# schematic.net
KiCad netlist of a schematic drawn in EAGLE
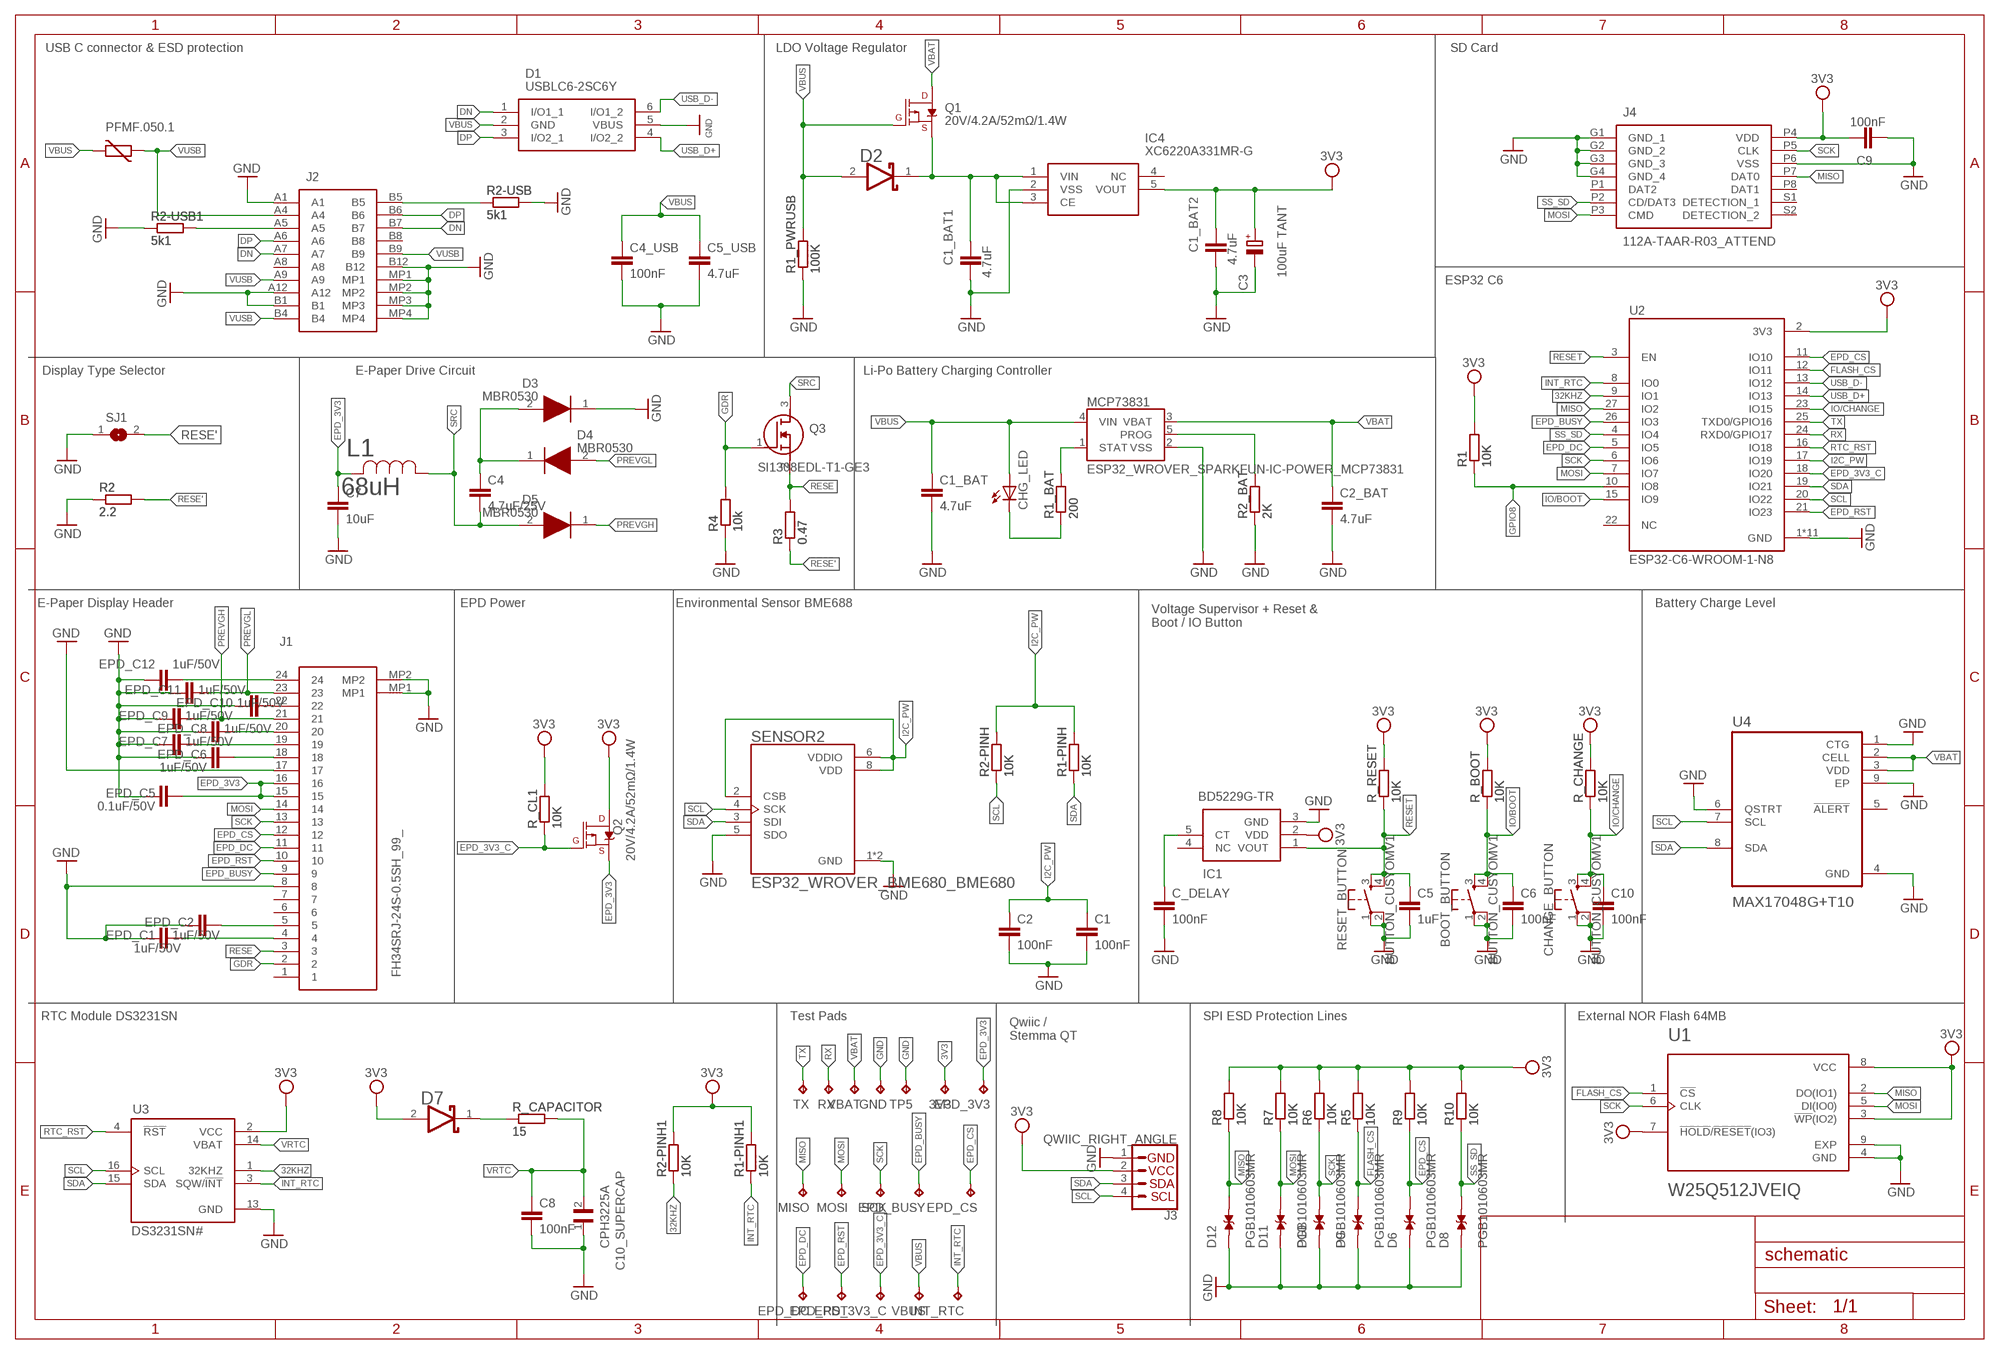
[diagram p0: schematic, sheet 1]

(export (version "E")
  (design (tool "Eeschema 10.0.6"))
  (components
    (comp (ref "3V3")
      (value "TPTP20R")
      (footprint "eagle-import:TP20R")
      (libsource (lib "eagle-import") (part "TPTP20R"))
    )
    (comp (ref "BOOT_BUTTON")
      (value "BUTTON_CUSYOMV1")
      (footprint "eagle-import:MYBUTTON")
      (libsource (lib "eagle-import") (part "BUTTON_CUSYOMV1"))
    )
    (comp (ref "C1")
      (value "100nF")
      (footprint "eagle-import:EAGLE-LTSPICE_C0402")
      (libsource (lib "eagle-import") (part "ESP32_WROVER_EAGLE-LTSPICE_CC0402"))
    )
    (comp (ref "C1_BAT")
      (value "4.7uF")
      (footprint "eagle-import:EAGLE-LTSPICE_C0402")
      (libsource (lib "eagle-import") (part "ESP32_WROVER_EAGLE-LTSPICE_CC0402"))
    )
    (comp (ref "C1_BAT1")
      (value "4.7uF")
      (footprint "eagle-import:ESP32_WROVER_EAGLE-LTSPICE_C0402")
      (libsource (lib "eagle-import") (part "DeskAssistant v19 v1_vf.dFvje_iDQXiLOtX_eNBvag_EAGLE-LTSPICE_CC0402"))
    )
    (comp (ref "C1_BAT2")
      (value "4.7uF")
      (footprint "eagle-import:ESP32_WROVER_EAGLE-LTSPICE_C0402")
      (libsource (lib "eagle-import") (part "DeskAssistant v19 v1_vf.dFvje_iDQXiLOtX_eNBvag_EAGLE-LTSPICE_CC0402"))
    )
    (comp (ref "C2")
      (value "100nF")
      (footprint "eagle-import:EAGLE-LTSPICE_C0402")
      (libsource (lib "eagle-import") (part "ESP32_WROVER_EAGLE-LTSPICE_CC0402"))
    )
    (comp (ref "C2_BAT")
      (value "4.7uF")
      (footprint "eagle-import:EAGLE-LTSPICE_C0402")
      (libsource (lib "eagle-import") (part "ESP32_WROVER_EAGLE-LTSPICE_CC0402"))
    )
    (comp (ref "C3")
      (value "100uF TANT")
      (footprint "eagle-import:RCL_CT3528")
      (libsource (lib "eagle-import") (part "RCL_CPOL-EUCT3528"))
    )
    (comp (ref "C4")
      (value "4.7uF/25V")
      (footprint "eagle-import:EAGLE-LTSPICE_C0402")
      (libsource (lib "eagle-import") (part "ESP32_WROVER_EAGLE-LTSPICE_CC0402"))
    )
    (comp (ref "C4_USB")
      (value "100nF")
      (footprint "eagle-import:EAGLE-LTSPICE_C0402")
      (libsource (lib "eagle-import") (part "EAGLE-LTSPICE_CC0402"))
    )
    (comp (ref "C5")
      (value "1uF")
      (footprint "eagle-import:EAGLE-LTSPICE_C0402")
      (libsource (lib "eagle-import") (part "ESP32_WROVER_EAGLE-LTSPICE_CC0402"))
    )
    (comp (ref "C5_USB")
      (value "4.7uF")
      (footprint "eagle-import:EAGLE-LTSPICE_C0402")
      (libsource (lib "eagle-import") (part "EAGLE-LTSPICE_CC0402"))
    )
    (comp (ref "C6")
      (value "100nF")
      (footprint "eagle-import:EAGLE-LTSPICE_C0402")
      (libsource (lib "eagle-import") (part "ESP32_WROVER_EAGLE-LTSPICE_CC0402"))
    )
    (comp (ref "C7")
      (value "10uF")
      (footprint "eagle-import:EAGLE-LTSPICE_C0402")
      (libsource (lib "eagle-import") (part "ESP32_WROVER_EAGLE-LTSPICE_CC0402"))
    )
    (comp (ref "C8")
      (value "100nF")
      (footprint "eagle-import:EAGLE-LTSPICE_C0402")
      (libsource (lib "eagle-import") (part "ESP32_WROVER_EAGLE-LTSPICE_CC0402"))
    )
    (comp (ref "C9")
      (value "100nF")
      (footprint "eagle-import:ESP32_WROVER_EAGLE-LTSPICE_C0402")
      (libsource (lib "eagle-import") (part "DeskAssistant v19 v1_vf.dFvje_iDQXiLOtX_eNBvag_EAGLE-LTSPICE_CC0402"))
    )
    (comp (ref "C10")
      (value "100nF")
      (footprint "eagle-import:EAGLE-LTSPICE_C0402")
      (libsource (lib "eagle-import") (part "ESP32_WROVER_EAGLE-LTSPICE_CC0402"))
    )
    (comp (ref "C10_SUPERCAP")
      (value "CPH3225A")
      (footprint "eagle-import:CAPCP3225X100N")
      (fields (field (name "MF") "Seiko Instruments"))
      (libsource (lib "eagle-import") (part "CPH3225A"))
    )
    (comp (ref "CHANGE_BUTTON")
      (value "BUTTON_CUSYOMV1")
      (footprint "eagle-import:MYBUTTON")
      (libsource (lib "eagle-import") (part "BUTTON_CUSYOMV1"))
    )
    (comp (ref "CHG_LED")
      (value "ADAFRUIT_LEDCHIP-LED0603")
      (footprint "eagle-import:ADAFRUIT_CHIP-LED0603")
      (libsource (lib "eagle-import") (part "ADAFRUIT_LEDCHIP-LED0603"))
    )
    (comp (ref "C_DELAY")
      (value "100nF")
      (footprint "eagle-import:EAGLE-LTSPICE_C0402")
      (libsource (lib "eagle-import") (part "ESP32_WROVER_EAGLE-LTSPICE_CC0402"))
    )
    (comp (ref "D1")
      (value "USBLC6-2SC6Y")
      (footprint "eagle-import:SOT95P280X145-6N")
      (fields (field (name "MF") "STMicroelectronics"))
      (libsource (lib "eagle-import") (part "USBLC6-2SC6Y"))
    )
    (comp (ref "D2")
      (value "ESP32_WROVER_AVX---SD0805S020S1R0_AVX_SD0805S020S1R0_0_0AVX_SD0805S020S1R0_0_0")
      (footprint "eagle-import:ESP32_WROVER_AVX---SD0805S020S1R0_AVX_SD0805S020S1R0_0")
      (fields
        (field (name "DIGIKEY_PART_NUMBER") "478-7800-1-ND")
        (field (name "MF") "AVX")
        (field (name "MOUSER_PART_NUMBER") "581-SD0805S020S1R0")
      )
      (libsource (lib "eagle-import") (part "ESP32_WROVER_AVX---SD0805S020S1R0_AVX_SD0805S020S1R0_0_0AVX_SD0805S020S1R0_0_0"))
    )
    (comp (ref "D3")
      (value "MBR0530")
      (footprint "eagle-import:SOD3716X135N")
      (fields (field (name "MF") "ON Semiconductor"))
      (libsource (lib "eagle-import") (part "MBR0530"))
    )
    (comp (ref "D4")
      (value "MBR0530")
      (footprint "eagle-import:SOD3716X135N")
      (fields (field (name "MF") "ON Semiconductor"))
      (libsource (lib "eagle-import") (part "MBR0530"))
    )
    (comp (ref "D5")
      (value "MBR0530")
      (footprint "eagle-import:SOD3716X135N")
      (fields (field (name "MF") "ON Semiconductor"))
      (libsource (lib "eagle-import") (part "MBR0530"))
    )
    (comp (ref "D6")
      (value "PGB1010603MR")
      (footprint "eagle-import:DIOC1608X36N")
      (fields (field (name "MF") "Littelfuse Inc."))
      (libsource (lib "eagle-import") (part "PGB1010603MR"))
    )
    (comp (ref "D7")
      (value "ESP32_WROVER_AVX---SD0805S020S1R0_AVX_SD0805S020S1R0_0_0AVX_SD0805S020S1R0_0_0")
      (footprint "eagle-import:ESP32_WROVER_AVX---SD0805S020S1R0_AVX_SD0805S020S1R0_0")
      (fields
        (field (name "DIGIKEY_PART_NUMBER") "478-7800-1-ND")
        (field (name "MF") "AVX")
        (field (name "MOUSER_PART_NUMBER") "581-SD0805S020S1R0")
      )
      (libsource (lib "eagle-import") (part "ESP32_WROVER_AVX---SD0805S020S1R0_AVX_SD0805S020S1R0_0_0AVX_SD0805S020S1R0_0_0"))
    )
    (comp (ref "D8")
      (value "PGB1010603MR")
      (footprint "eagle-import:DIOC1608X36N")
      (fields (field (name "MF") "Littelfuse Inc."))
      (libsource (lib "eagle-import") (part "PGB1010603MR"))
    )
    (comp (ref "D9")
      (value "PGB1010603MR")
      (footprint "eagle-import:DIOC1608X36N")
      (fields (field (name "MF") "Littelfuse Inc."))
      (libsource (lib "eagle-import") (part "PGB1010603MR"))
    )
    (comp (ref "D10")
      (value "PGB1010603MR")
      (footprint "eagle-import:DIOC1608X36N")
      (fields (field (name "MF") "Littelfuse Inc."))
      (libsource (lib "eagle-import") (part "PGB1010603MR"))
    )
    (comp (ref "D11")
      (value "PGB1010603MR")
      (footprint "eagle-import:DIOC1608X36N")
      (fields (field (name "MF") "Littelfuse Inc."))
      (libsource (lib "eagle-import") (part "PGB1010603MR"))
    )
    (comp (ref "D12")
      (value "PGB1010603MR")
      (footprint "eagle-import:DIOC1608X36N")
      (fields (field (name "MF") "Littelfuse Inc."))
      (libsource (lib "eagle-import") (part "PGB1010603MR"))
    )
    (comp (ref "EPD_3V3")
      (value "TPTP20R")
      (footprint "eagle-import:TP20R")
      (libsource (lib "eagle-import") (part "TPTP20R"))
    )
    (comp (ref "EPD_3V3_C")
      (value "TPTP20R")
      (footprint "eagle-import:TP20R")
      (libsource (lib "eagle-import") (part "TPTP20R"))
    )
    (comp (ref "EPD_BUSY")
      (value "TPTP20R")
      (footprint "eagle-import:TP20R")
      (libsource (lib "eagle-import") (part "TPTP20R"))
    )
    (comp (ref "EPD_C1")
      (value "1uF/50V")
      (footprint "eagle-import:EAGLE-LTSPICE_C0402")
      (libsource (lib "eagle-import") (part "ESP32_WROVER_EAGLE-LTSPICE_CC0402"))
    )
    (comp (ref "EPD_C2")
      (value "1uF/50V")
      (footprint "eagle-import:EAGLE-LTSPICE_C0402")
      (libsource (lib "eagle-import") (part "ESP32_WROVER_EAGLE-LTSPICE_CC0402"))
    )
    (comp (ref "EPD_C5")
      (value "0.1uF/50V")
      (footprint "eagle-import:EAGLE-LTSPICE_C0402")
      (libsource (lib "eagle-import") (part "ESP32_WROVER_EAGLE-LTSPICE_CC0402"))
    )
    (comp (ref "EPD_C6")
      (value "1uF/50V")
      (footprint "eagle-import:EAGLE-LTSPICE_C0402")
      (libsource (lib "eagle-import") (part "ESP32_WROVER_EAGLE-LTSPICE_CC0402"))
    )
    (comp (ref "EPD_C7")
      (value "1uF/50V")
      (footprint "eagle-import:EAGLE-LTSPICE_C0402")
      (libsource (lib "eagle-import") (part "ESP32_WROVER_EAGLE-LTSPICE_CC0402"))
    )
    (comp (ref "EPD_C8")
      (value "1uF/50V")
      (footprint "eagle-import:EAGLE-LTSPICE_C0402")
      (libsource (lib "eagle-import") (part "ESP32_WROVER_EAGLE-LTSPICE_CC0402"))
    )
    (comp (ref "EPD_C9")
      (value "1uF/50V")
      (footprint "eagle-import:EAGLE-LTSPICE_C0402")
      (libsource (lib "eagle-import") (part "ESP32_WROVER_EAGLE-LTSPICE_CC0402"))
    )
    (comp (ref "EPD_C10")
      (value "1uF/50V")
      (footprint "eagle-import:EAGLE-LTSPICE_C0402")
      (libsource (lib "eagle-import") (part "ESP32_WROVER_EAGLE-LTSPICE_CC0402"))
    )
    (comp (ref "EPD_C11")
      (value "1uF/50V")
      (footprint "eagle-import:EAGLE-LTSPICE_C0402")
      (libsource (lib "eagle-import") (part "ESP32_WROVER_EAGLE-LTSPICE_CC0402"))
    )
    (comp (ref "EPD_C12")
      (value "1uF/50V")
      (footprint "eagle-import:EAGLE-LTSPICE_C0402")
      (libsource (lib "eagle-import") (part "ESP32_WROVER_EAGLE-LTSPICE_CC0402"))
    )
    (comp (ref "EPD_CS")
      (value "TPTP20R")
      (footprint "eagle-import:TP20R")
      (libsource (lib "eagle-import") (part "TPTP20R"))
    )
    (comp (ref "EPD_DC")
      (value "TPTP20R")
      (footprint "eagle-import:TP20R")
      (libsource (lib "eagle-import") (part "TPTP20R"))
    )
    (comp (ref "EPD_RST")
      (value "TPTP20R")
      (footprint "eagle-import:TP20R")
      (libsource (lib "eagle-import") (part "TPTP20R"))
    )
    (comp (ref "GND")
      (value "TPTP20R")
      (footprint "eagle-import:TP20R")
      (libsource (lib "eagle-import") (part "TPTP20R"))
    )
    (comp (ref "IC1")
      (value "BD5229G-TR")
      (footprint "eagle-import:SOT95P280X125-5N")
      (fields (field (name "MOUSER_PART_NUMBER") "755-BD5229G-TR"))
      (libsource (lib "eagle-import") (part "BD5229G-TR"))
    )
    (comp (ref "IC4")
      (value "XC6220A331MR-G")
      (footprint "eagle-import:SOT95P280X120-5N")
      (fields (field (name "MOUSER_PART_NUMBER") "865-XC6220A331MR-G"))
      (libsource (lib "eagle-import") (part "XC6220A331MR-G"))
    )
    (comp (ref "INT_RTC")
      (value "TPTP20R")
      (footprint "eagle-import:TP20R")
      (libsource (lib "eagle-import") (part "TPTP20R"))
    )
    (comp (ref "J1")
      (value "FH34SRJ-24S-0.5SH_99_")
      (footprint "eagle-import:FH34SRJ24S05SH99")
      (fields
        (field (name "MANUFACTURER_PART_NUMBER") "FH34SRJ-24S-0.5SH(99)")
        (field (name "MOUSER_PART_NUMBER") "798-FH34SRJ24S05SH99")
      )
      (libsource (lib "eagle-import") (part "FH34SRJ-24S-0.5SH_99_"))
    )
    (comp (ref "J2")
      (value "SAMACSYS_PARTS_USB4110-GF-A")
      (footprint "eagle-import:SAMACSYS_PARTS_USB4110GFA")
      (fields
        (field (name "MANUFACTURER_PART_NUMBER") "USB4110-GF-A")
        (field (name "MOUSER_PART_NUMBER") "640-USB4110-GF-A")
      )
      (libsource (lib "eagle-import") (part "SAMACSYS_PARTS_USB4110-GF-A"))
    )
    (comp (ref "J3")
      (value "QWIIC_RIGHT_ANGLE")
      (footprint "eagle-import:JST04_1MM_RA")
      (libsource (lib "eagle-import") (part "QWIIC_CONNECTORJS-1MM"))
    )
    (comp (ref "J4")
      (value "112A-TAAR-R03_ATTEND")
      (footprint "eagle-import:112ATAARR03ATTEND")
      (fields (field (name "MANUFACTURER_PART_NUMBER") "112A-TAAR-R03 ATTEND"))
      (libsource (lib "eagle-import") (part "112A-TAAR-R03_ATTEND"))
    )
    (comp (ref "L1")
      (value "68uH")
      (footprint "eagle-import:IND_4828-WE-TPC_WRE")
      (fields
        (field (name "MANUFACTURER_PART_NUMBER") "744043680")
        (field (name "COPYRIGHT") "Copyright (C) 2024 Ultra Librarian. All rights reserved.")
      )
      (libsource (lib "eagle-import") (part "744043680IND_4828-WE-TPC_WRE"))
    )
    (comp (ref "MCP73831")
      (value "ESP32_WROVER_SPARKFUN-IC-POWER_MCP73831")
      (footprint "eagle-import:ESP32_WROVER_SPARKFUN-IC-POWER_SOT23-5")
      (libsource (lib "eagle-import") (part "ESP32_WROVER_SPARKFUN-IC-POWER_MCP73831"))
    )
    (comp (ref "MISO")
      (value "TPTP20R")
      (footprint "eagle-import:TP20R")
      (libsource (lib "eagle-import") (part "TPTP20R"))
    )
    (comp (ref "MOSI")
      (value "TPTP20R")
      (footprint "eagle-import:TP20R")
      (libsource (lib "eagle-import") (part "TPTP20R"))
    )
    (comp (ref "PFMF.050.1")
      (value "ESP32C6_VARISTORCN1812")
      (footprint "eagle-import:ESP32C6_VARISTOR_CT_CN1812")
      (libsource (lib "eagle-import") (part "ESP32C6_VARISTORCN1812"))
    )
    (comp (ref "Q1")
      (value "20V/4.2A/52mΩ/1.4W")
      (footprint "eagle-import:ESP32_WROVER_SPARKFUN-DISCRETESEMI_SOT23-3")
      (libsource (lib "eagle-import") (part "ESP32_WROVER_SPARKFUN-DISCRETESEMI_MOSFET_PCH-DMG2305UX-7"))
    )
    (comp (ref "Q2")
      (value "20V/4.2A/52mΩ/1.4W")
      (footprint "eagle-import:ESP32_WROVER_SPARKFUN-DISCRETESEMI_SOT23-3")
      (libsource (lib "eagle-import") (part "ESP32_WROVER_SPARKFUN-DISCRETESEMI_MOSFET_PCH-DMG2305UX-7"))
    )
    (comp (ref "Q3")
      (value "SI1308EDL-T1-GE3")
      (footprint "eagle-import:SOT65P210X110-3N")
      (fields (field (name "MF") "Vishay Siliconix"))
      (libsource (lib "eagle-import") (part "SI1308EDL-T1-GE3"))
    )
    (comp (ref "R1")
      (value "10K")
      (footprint "eagle-import:ESP32_WROVER_EAGLE-LTSPICE_R0402")
      (libsource (lib "eagle-import") (part "DeskAssistant v19 v1_vf.dFvje_iDQXiLOtX_eNBvag_ESP32_WROVER_EAGLE-LTSPICE_RR0402"))
    )
    (comp (ref "R1-PINH")
      (value "10K")
      (footprint "eagle-import:ESP32_WROVER_EAGLE-LTSPICE_R0402")
      (libsource (lib "eagle-import") (part "DeskAssistant v19 v1_vf.dFvje_iDQXiLOtX_eNBvag_ESP32_WROVER_EAGLE-LTSPICE_RR0402"))
    )
    (comp (ref "R1-PINH1")
      (value "10K")
      (footprint "eagle-import:ESP32_WROVER_EAGLE-LTSPICE_R0402")
      (libsource (lib "eagle-import") (part "DeskAssistant v19 v1_vf.dFvje_iDQXiLOtX_eNBvag_ESP32_WROVER_EAGLE-LTSPICE_RR0402"))
    )
    (comp (ref "R1_BAT")
      (value "200")
      (footprint "eagle-import:ESP32_WROVER_EAGLE-LTSPICE_R0402")
      (libsource (lib "eagle-import") (part "DeskAssistant v19 v1_vf.dFvje_iDQXiLOtX_eNBvag_ESP32_WROVER_EAGLE-LTSPICE_RR0402"))
    )
    (comp (ref "R1_PWRUSB")
      (value "100K")
      (footprint "eagle-import:ESP32_WROVER_EAGLE-LTSPICE_R0402")
      (libsource (lib "eagle-import") (part "DeskAssistant v19 v1_vf.dFvje_iDQXiLOtX_eNBvag_ESP32_WROVER_EAGLE-LTSPICE_RR0402"))
    )
    (comp (ref "R2")
      (value "2.2")
      (footprint "eagle-import:ESP32_WROVER_EAGLE-LTSPICE_R0402")
      (libsource (lib "eagle-import") (part "DeskAssistant v19 v1_vf.dFvje_iDQXiLOtX_eNBvag_ESP32_WROVER_EAGLE-LTSPICE_RR0402"))
    )
    (comp (ref "R2-PINH")
      (value "10K")
      (footprint "eagle-import:ESP32_WROVER_EAGLE-LTSPICE_R0402")
      (libsource (lib "eagle-import") (part "DeskAssistant v19 v1_vf.dFvje_iDQXiLOtX_eNBvag_ESP32_WROVER_EAGLE-LTSPICE_RR0402"))
    )
    (comp (ref "R2-PINH1")
      (value "10K")
      (footprint "eagle-import:ESP32_WROVER_EAGLE-LTSPICE_R0402")
      (libsource (lib "eagle-import") (part "DeskAssistant v19 v1_vf.dFvje_iDQXiLOtX_eNBvag_ESP32_WROVER_EAGLE-LTSPICE_RR0402"))
    )
    (comp (ref "R2-USB")
      (value "5k1")
      (footprint "eagle-import:ESP32_WROVER_EAGLE-LTSPICE_R0402")
      (libsource (lib "eagle-import") (part "ESP32_WROVER_EAGLE-LTSPICE_RR0402"))
    )
    (comp (ref "R2-USB1")
      (value "5k1")
      (footprint "eagle-import:ESP32_WROVER_EAGLE-LTSPICE_R0402")
      (libsource (lib "eagle-import") (part "ESP32_WROVER_EAGLE-LTSPICE_RR0402"))
    )
    (comp (ref "R2_BAT")
      (value "2K")
      (footprint "eagle-import:ESP32_WROVER_EAGLE-LTSPICE_R0402")
      (libsource (lib "eagle-import") (part "DeskAssistant v19 v1_vf.dFvje_iDQXiLOtX_eNBvag_ESP32_WROVER_EAGLE-LTSPICE_RR0402"))
    )
    (comp (ref "R3")
      (value "0.47")
      (footprint "eagle-import:ESP32_WROVER_EAGLE-LTSPICE_R0402")
      (libsource (lib "eagle-import") (part "DeskAssistant v19 v1_vf.dFvje_iDQXiLOtX_eNBvag_ESP32_WROVER_EAGLE-LTSPICE_RR0402"))
    )
    (comp (ref "R4")
      (value "10k")
      (footprint "eagle-import:ESP32_WROVER_EAGLE-LTSPICE_R0402")
      (libsource (lib "eagle-import") (part "DeskAssistant v19 v1_vf.dFvje_iDQXiLOtX_eNBvag_ESP32_WROVER_EAGLE-LTSPICE_RR0402"))
    )
    (comp (ref "R5")
      (value "10K")
      (footprint "eagle-import:ESP32_WROVER_EAGLE-LTSPICE_R0402")
      (libsource (lib "eagle-import") (part "DeskAssistant v19 v1_vf.dFvje_iDQXiLOtX_eNBvag_ESP32_WROVER_EAGLE-LTSPICE_RR0402"))
    )
    (comp (ref "R6")
      (value "10K")
      (footprint "eagle-import:ESP32_WROVER_EAGLE-LTSPICE_R0402")
      (libsource (lib "eagle-import") (part "DeskAssistant v19 v1_vf.dFvje_iDQXiLOtX_eNBvag_ESP32_WROVER_EAGLE-LTSPICE_RR0402"))
    )
    (comp (ref "R7")
      (value "10K")
      (footprint "eagle-import:ESP32_WROVER_EAGLE-LTSPICE_R0402")
      (libsource (lib "eagle-import") (part "DeskAssistant v19 v1_vf.dFvje_iDQXiLOtX_eNBvag_ESP32_WROVER_EAGLE-LTSPICE_RR0402"))
    )
    (comp (ref "R8")
      (value "10K")
      (footprint "eagle-import:ESP32_WROVER_EAGLE-LTSPICE_R0402")
      (libsource (lib "eagle-import") (part "DeskAssistant v19 v1_vf.dFvje_iDQXiLOtX_eNBvag_ESP32_WROVER_EAGLE-LTSPICE_RR0402"))
    )
    (comp (ref "R9")
      (value "10K")
      (footprint "eagle-import:ESP32_WROVER_EAGLE-LTSPICE_R0402")
      (libsource (lib "eagle-import") (part "DeskAssistant v19 v1_vf.dFvje_iDQXiLOtX_eNBvag_ESP32_WROVER_EAGLE-LTSPICE_RR0402"))
    )
    (comp (ref "R10")
      (value "10K")
      (footprint "eagle-import:ESP32_WROVER_EAGLE-LTSPICE_R0402")
      (libsource (lib "eagle-import") (part "DeskAssistant v19 v1_vf.dFvje_iDQXiLOtX_eNBvag_ESP32_WROVER_EAGLE-LTSPICE_RR0402"))
    )
    (comp (ref "RESET_BUTTON")
      (value "BUTTON_CUSYOMV1")
      (footprint "eagle-import:MYBUTTON")
      (libsource (lib "eagle-import") (part "BUTTON_CUSYOMV1"))
    )
    (comp (ref "RX")
      (value "TPTP20R")
      (footprint "eagle-import:TP20R")
      (libsource (lib "eagle-import") (part "TPTP20R"))
    )
    (comp (ref "R_BOOT")
      (value "10K")
      (footprint "eagle-import:ESP32_WROVER_EAGLE-LTSPICE_R0402")
      (libsource (lib "eagle-import") (part "DeskAssistant v19 v1_vf.dFvje_iDQXiLOtX_eNBvag_ESP32_WROVER_EAGLE-LTSPICE_RR0402"))
    )
    (comp (ref "R_CAPACITOR")
      (value "15")
      (footprint "eagle-import:ESP32_WROVER_EAGLE-LTSPICE_R0402")
      (libsource (lib "eagle-import") (part "DeskAssistant v19 v1_vf.dFvje_iDQXiLOtX_eNBvag_ESP32_WROVER_EAGLE-LTSPICE_RR0402"))
    )
    (comp (ref "R_CHANGE")
      (value "10K")
      (footprint "eagle-import:ESP32_WROVER_EAGLE-LTSPICE_R0402")
      (libsource (lib "eagle-import") (part "DeskAssistant v19 v1_vf.dFvje_iDQXiLOtX_eNBvag_ESP32_WROVER_EAGLE-LTSPICE_RR0402"))
    )
    (comp (ref "R_CL1")
      (value "10K")
      (footprint "eagle-import:ESP32_WROVER_EAGLE-LTSPICE_R0402")
      (libsource (lib "eagle-import") (part "DeskAssistant v19 v1_vf.dFvje_iDQXiLOtX_eNBvag_ESP32_WROVER_EAGLE-LTSPICE_RR0402"))
    )
    (comp (ref "R_RESET")
      (value "10K")
      (footprint "eagle-import:ESP32_WROVER_EAGLE-LTSPICE_R0402")
      (libsource (lib "eagle-import") (part "DeskAssistant v19 v1_vf.dFvje_iDQXiLOtX_eNBvag_ESP32_WROVER_EAGLE-LTSPICE_RR0402"))
    )
    (comp (ref "SCK")
      (value "TPTP20R")
      (footprint "eagle-import:TP20R")
      (libsource (lib "eagle-import") (part "TPTP20R"))
    )
    (comp (ref "SENSOR2")
      (value "ESP32_WROVER_BME680_BME680")
      (footprint "eagle-import:ESP32_WROVER_BME680_PSON80P300X300X100-8N")
      (fields (field (name "MF") "Bosch Sensortec") (field (name "MP") "BME680"))
      (libsource (lib "eagle-import") (part "ESP32_WROVER_BME680_BME680"))
    )
    (comp (ref "SJ1") (value "SJ") (footprint "eagle-import:SJ") (libsource (lib "eagle-import") (part "SJ")))
    (comp (ref "TP5")
      (value "TPTP20R")
      (footprint "eagle-import:TP20R")
      (libsource (lib "eagle-import") (part "TPTP20R"))
    )
    (comp (ref "TX")
      (value "TPTP20R")
      (footprint "eagle-import:TP20R")
      (libsource (lib "eagle-import") (part "TPTP20R"))
    )
    (comp (ref "U1")
      (value "W25Q512JVEIQ")
      (footprint "eagle-import:SON127P600X800X80-9N")
      (fields (field (name "MF") "Winbond Electronics"))
      (libsource (lib "eagle-import") (part "W25Q512JVEIQ"))
    )
    (comp (ref "U2")
      (value "ESP32-C6-WROOM-1-N8")
      (footprint "eagle-import:XCVR_ESP32-C6-WROOM-1-N8")
      (fields (field (name "MF") "Espressif Systems"))
      (libsource (lib "eagle-import") (part "ESP32-C6-WROOM-1-N8"))
    )
    (comp (ref "U3")
      (value "DS3231SN#")
      (footprint "eagle-import:SOIC127P1032X265-16N")
      (fields (field (name "MF") "Analog Devices"))
      (libsource (lib "eagle-import") (part "DS3231SN#"))
    )
    (comp (ref "U4")
      (value "MAX17048G+T10")
      (footprint "eagle-import:SON50P200X200X80-9N")
      (fields (field (name "MF") "Analog Devices"))
      (libsource (lib "eagle-import") (part "MAX17048G+T10"))
    )
    (comp (ref "VBAT")
      (value "TPTP20R")
      (footprint "eagle-import:TP20R")
      (libsource (lib "eagle-import") (part "TPTP20R"))
    )
    (comp (ref "VBUS")
      (value "TPTP20R")
      (footprint "eagle-import:TP20R")
      (libsource (lib "eagle-import") (part "TPTP20R"))
    )
  )
  (nets
    (net (code "1") (name "3V3") (class "Default")
      (node (ref "3V3") (pin "TP") (pinfunction "TP_TP") (pintype "input"))
      (node (ref "C1_BAT2") (pin "1") (pinfunction "1_1") (pintype "passive"))
      (node (ref "C3") (pin "+") (pinfunction "+_+") (pintype "passive"))
      (node (ref "C9") (pin "1") (pinfunction "1_1") (pintype "passive"))
      (node (ref "D7") (pin "2") (pinfunction "ANODE_2") (pintype "bidirectional"))
      (node (ref "IC1") (pin "2") (pinfunction "VDD_2") (pintype "bidirectional"))
      (node (ref "IC4") (pin "5") (pinfunction "VOUT_5") (pintype "bidirectional"))
      (node (ref "J3") (pin "2") (pinfunction "2_2") (pintype "power_in"))
      (node (ref "J4") (pin "P4") (pinfunction "VDD_P4") (pintype "bidirectional"))
      (node (ref "Q2") (pin "3") (pinfunction "D_3") (pintype "bidirectional"))
      (node (ref "R1") (pin "2") (pinfunction "2_2") (pintype "passive"))
      (node (ref "R1-PINH1") (pin "2") (pinfunction "2_2") (pintype "passive"))
      (node (ref "R10") (pin "2") (pinfunction "2_2") (pintype "passive"))
      (node (ref "R2-PINH1") (pin "2") (pinfunction "2_2") (pintype "passive"))
      (node (ref "R5") (pin "2") (pinfunction "2_2") (pintype "passive"))
      (node (ref "R6") (pin "2") (pinfunction "2_2") (pintype "passive"))
      (node (ref "R7") (pin "2") (pinfunction "2_2") (pintype "passive"))
      (node (ref "R8") (pin "2") (pinfunction "2_2") (pintype "passive"))
      (node (ref "R9") (pin "2") (pinfunction "2_2") (pintype "passive"))
      (node (ref "R_BOOT") (pin "2") (pinfunction "2_2") (pintype "passive"))
      (node (ref "R_CHANGE") (pin "2") (pinfunction "2_2") (pintype "passive"))
      (node (ref "R_CL1") (pin "2") (pinfunction "2_2") (pintype "passive"))
      (node (ref "R_RESET") (pin "2") (pinfunction "2_2") (pintype "passive"))
      (node (ref "U1") (pin "3") (pinfunction "~{WP}(IO2)_3") (pintype "bidirectional"))
      (node (ref "U1") (pin "7") (pinfunction "~{HOLD}/~{RESET}(IO3)_7") (pintype "bidirectional"))
      (node (ref "U1") (pin "8") (pinfunction "VCC_8") (pintype "power_in"))
      (node (ref "U2") (pin "2") (pinfunction "3V3_2") (pintype "power_in"))
      (node (ref "U3") (pin "2") (pinfunction "VCC_2") (pintype "power_in"))
    )
    (net (code "2") (name "32KHZ") (class "Default")
      (node (ref "R2-PINH1") (pin "1") (pinfunction "1_1") (pintype "passive"))
      (node (ref "U2") (pin "9") (pinfunction "IO1_9") (pintype "bidirectional"))
      (node (ref "U3") (pin "1") (pinfunction "32KHZ_1") (pintype "output"))
    )
    (net (code "3") (name "DN") (class "Default")
      (node (ref "D1") (pin "1") (pinfunction "I/O1_1_1") (pintype "bidirectional"))
      (node (ref "J2") (pin "A7") (pinfunction "A7_A7") (pintype "bidirectional"))
      (node (ref "J2") (pin "B7") (pinfunction "B7_B7") (pintype "bidirectional"))
    )
    (net (code "4") (name "DP") (class "Default")
      (node (ref "D1") (pin "3") (pinfunction "I/O2_1_3") (pintype "bidirectional"))
      (node (ref "J2") (pin "A6") (pinfunction "A6_A6") (pintype "bidirectional"))
      (node (ref "J2") (pin "B6") (pinfunction "B6_B6") (pintype "bidirectional"))
    )
    (net (code "5") (name "EPD_3V3") (class "Default")
      (node (ref "C7") (pin "1") (pinfunction "1_1") (pintype "passive"))
      (node (ref "EPD_3V3") (pin "TP") (pinfunction "TP_TP") (pintype "input"))
      (node (ref "EPD_C5") (pin "2") (pinfunction "2_2") (pintype "passive"))
      (node (ref "J1") (pin "15") (pinfunction "15_15") (pintype "bidirectional"))
      (node (ref "J1") (pin "16") (pinfunction "16_16") (pintype "bidirectional"))
      (node (ref "L1") (pin "2") (pinfunction "2_2") (pintype "passive"))
      (node (ref "Q2") (pin "2") (pinfunction "S_2") (pintype "bidirectional"))
    )
    (net (code "6") (name "EPD_3V3_C") (class "Default")
      (node (ref "EPD_3V3_C") (pin "TP") (pinfunction "TP_TP") (pintype "input"))
      (node (ref "Q2") (pin "1") (pinfunction "G_1") (pintype "bidirectional"))
      (node (ref "R_CL1") (pin "1") (pinfunction "1_1") (pintype "passive"))
      (node (ref "U2") (pin "18") (pinfunction "IO20_18") (pintype "bidirectional"))
    )
    (net (code "7") (name "EPD_BUSY") (class "Default")
      (node (ref "EPD_BUSY") (pin "TP") (pinfunction "TP_TP") (pintype "input"))
      (node (ref "J1") (pin "9") (pinfunction "9_9") (pintype "bidirectional"))
      (node (ref "U2") (pin "26") (pinfunction "IO3_26") (pintype "bidirectional"))
    )
    (net (code "8") (name "EPD_CS") (class "Default")
      (node (ref "D6") (pin "2") (pinfunction "2_2") (pintype "passive"))
      (node (ref "EPD_CS") (pin "TP") (pinfunction "TP_TP") (pintype "input"))
      (node (ref "J1") (pin "12") (pinfunction "12_12") (pintype "bidirectional"))
      (node (ref "R9") (pin "1") (pinfunction "1_1") (pintype "passive"))
      (node (ref "U2") (pin "11") (pinfunction "IO10_11") (pintype "bidirectional"))
    )
    (net (code "9") (name "EPD_DC") (class "Default")
      (node (ref "EPD_DC") (pin "TP") (pinfunction "TP_TP") (pintype "input"))
      (node (ref "J1") (pin "11") (pinfunction "11_11") (pintype "bidirectional"))
      (node (ref "U2") (pin "5") (pinfunction "IO5_5") (pintype "bidirectional"))
    )
    (net (code "10") (name "EPD_RST") (class "Default")
      (node (ref "EPD_RST") (pin "TP") (pinfunction "TP_TP") (pintype "input"))
      (node (ref "J1") (pin "10") (pinfunction "10_10") (pintype "bidirectional"))
      (node (ref "U2") (pin "21") (pinfunction "IO23_21") (pintype "bidirectional"))
    )
    (net (code "11") (name "FLASH_CS") (class "Default")
      (node (ref "D9") (pin "2") (pinfunction "2_2") (pintype "passive"))
      (node (ref "R5") (pin "1") (pinfunction "1_1") (pintype "passive"))
      (node (ref "U1") (pin "1") (pinfunction "~{CS}_1") (pintype "input"))
      (node (ref "U2") (pin "12") (pinfunction "IO11_12") (pintype "bidirectional"))
    )
    (net (code "12") (name "GDR") (class "Default")
      (node (ref "J1") (pin "2") (pinfunction "2_2") (pintype "bidirectional"))
      (node (ref "Q3") (pin "1") (pinfunction "G_1") (pintype "bidirectional"))
      (node (ref "R4") (pin "2") (pinfunction "2_2") (pintype "passive"))
    )
    (net (code "13") (name "GND") (class "Default")
      (node (ref "BOOT_BUTTON") (pin "1") (pinfunction "1_1") (pintype "passive"))
      (node (ref "BOOT_BUTTON") (pin "2") (pinfunction "2_2") (pintype "passive"))
      (node (ref "C1") (pin "2") (pinfunction "2_2") (pintype "passive"))
      (node (ref "C10") (pin "2") (pinfunction "2_2") (pintype "passive"))
      (node (ref "C10_SUPERCAP") (pin "1") (pinfunction "1_1") (pintype "passive"))
      (node (ref "C1_BAT") (pin "2") (pinfunction "2_2") (pintype "passive"))
      (node (ref "C1_BAT1") (pin "2") (pinfunction "2_2") (pintype "passive"))
      (node (ref "C1_BAT2") (pin "2") (pinfunction "2_2") (pintype "passive"))
      (node (ref "C2") (pin "2") (pinfunction "2_2") (pintype "passive"))
      (node (ref "C2_BAT") (pin "2") (pinfunction "2_2") (pintype "passive"))
      (node (ref "C3") (pin "-") (pinfunction "-_-") (pintype "passive"))
      (node (ref "C4_USB") (pin "2") (pinfunction "2_2") (pintype "passive"))
      (node (ref "C5") (pin "2") (pinfunction "2_2") (pintype "passive"))
      (node (ref "C5_USB") (pin "2") (pinfunction "2_2") (pintype "passive"))
      (node (ref "C6") (pin "2") (pinfunction "2_2") (pintype "passive"))
      (node (ref "C7") (pin "2") (pinfunction "2_2") (pintype "passive"))
      (node (ref "C8") (pin "2") (pinfunction "2_2") (pintype "passive"))
      (node (ref "C9") (pin "2") (pinfunction "2_2") (pintype "passive"))
      (node (ref "CHANGE_BUTTON") (pin "1") (pinfunction "1_1") (pintype "passive"))
      (node (ref "CHANGE_BUTTON") (pin "2") (pinfunction "2_2") (pintype "passive"))
      (node (ref "C_DELAY") (pin "2") (pinfunction "2_2") (pintype "passive"))
      (node (ref "D1") (pin "5") (pinfunction "VBUS_5") (pintype "bidirectional"))
      (node (ref "D10") (pin "1") (pinfunction "1_1") (pintype "passive"))
      (node (ref "D11") (pin "1") (pinfunction "1_1") (pintype "passive"))
      (node (ref "D12") (pin "1") (pinfunction "1_1") (pintype "passive"))
      (node (ref "D3") (pin "1") (pinfunction "K_1") (pintype "bidirectional"))
      (node (ref "D6") (pin "1") (pinfunction "1_1") (pintype "passive"))
      (node (ref "D8") (pin "1") (pinfunction "1_1") (pintype "passive"))
      (node (ref "D9") (pin "1") (pinfunction "1_1") (pintype "passive"))
      (node (ref "EPD_C1") (pin "1") (pinfunction "1_1") (pintype "passive"))
      (node (ref "EPD_C10") (pin "1") (pinfunction "1_1") (pintype "passive"))
      (node (ref "EPD_C11") (pin "1") (pinfunction "1_1") (pintype "passive"))
      (node (ref "EPD_C12") (pin "1") (pinfunction "1_1") (pintype "passive"))
      (node (ref "EPD_C2") (pin "1") (pinfunction "1_1") (pintype "passive"))
      (node (ref "EPD_C5") (pin "1") (pinfunction "1_1") (pintype "passive"))
      (node (ref "EPD_C6") (pin "1") (pinfunction "1_1") (pintype "passive"))
      (node (ref "EPD_C7") (pin "1") (pinfunction "1_1") (pintype "passive"))
      (node (ref "EPD_C8") (pin "1") (pinfunction "1_1") (pintype "passive"))
      (node (ref "EPD_C9") (pin "1") (pinfunction "1_1") (pintype "passive"))
      (node (ref "GND") (pin "TP") (pinfunction "TP_TP") (pintype "input"))
      (node (ref "IC1") (pin "3") (pinfunction "GND_3") (pintype "bidirectional"))
      (node (ref "IC4") (pin "2") (pinfunction "VSS_2") (pintype "bidirectional"))
      (node (ref "J1") (pin "17") (pinfunction "17_17") (pintype "bidirectional"))
      (node (ref "J1") (pin "8") (pinfunction "8_8") (pintype "bidirectional"))
      (node (ref "J1") (pin "MP1") (pinfunction "MP1_MP1") (pintype "bidirectional"))
      (node (ref "J1") (pin "MP2") (pinfunction "MP2_MP2") (pintype "bidirectional"))
      (node (ref "J2") (pin "A1") (pinfunction "A1_A1") (pintype "bidirectional"))
      (node (ref "J2") (pin "A12") (pinfunction "A12_A12") (pintype "bidirectional"))
      (node (ref "J2") (pin "B1") (pinfunction "B1_B1") (pintype "bidirectional"))
      (node (ref "J2") (pin "B12") (pinfunction "B12_B12") (pintype "bidirectional"))
      (node (ref "J2") (pin "MP1") (pinfunction "MP1_MP1") (pintype "bidirectional"))
      (node (ref "J2") (pin "MP2") (pinfunction "MP2_MP2") (pintype "bidirectional"))
      (node (ref "J2") (pin "MP3") (pinfunction "MP3_MP3") (pintype "bidirectional"))
      (node (ref "J2") (pin "MP4") (pinfunction "MP4_MP4") (pintype "bidirectional"))
      (node (ref "J3") (pin "1") (pinfunction "1_1") (pintype "power_in"))
      (node (ref "J4") (pin "G1") (pinfunction "GND_1_G1") (pintype "bidirectional"))
      (node (ref "J4") (pin "G2") (pinfunction "GND_2_G2") (pintype "bidirectional"))
      (node (ref "J4") (pin "G3") (pinfunction "GND_3_G3") (pintype "bidirectional"))
      (node (ref "J4") (pin "G4") (pinfunction "GND_4_G4") (pintype "bidirectional"))
      (node (ref "J4") (pin "P6") (pinfunction "VSS_P6") (pintype "bidirectional"))
      (node (ref "MCP73831") (pin "2") (pinfunction "VSS_2") (pintype "power_in"))
      (node (ref "R1_PWRUSB") (pin "1") (pinfunction "1_1") (pintype "passive"))
      (node (ref "R2") (pin "1") (pinfunction "1_1") (pintype "passive"))
      (node (ref "R2-USB") (pin "2") (pinfunction "2_2") (pintype "passive"))
      (node (ref "R2-USB1") (pin "1") (pinfunction "1_1") (pintype "passive"))
      (node (ref "R2_BAT") (pin "1") (pinfunction "1_1") (pintype "passive"))
      (node (ref "R4") (pin "1") (pinfunction "1_1") (pintype "passive"))
      (node (ref "RESET_BUTTON") (pin "1") (pinfunction "1_1") (pintype "passive"))
      (node (ref "RESET_BUTTON") (pin "2") (pinfunction "2_2") (pintype "passive"))
      (node (ref "SENSOR2") (pin "1") (pinfunction "GND_1") (pintype "power_in"))
      (node (ref "SENSOR2") (pin "5") (pinfunction "SDO_5") (pintype "bidirectional"))
      (node (ref "SENSOR2") (pin "7") (pinfunction "GND_7") (pintype "power_in"))
      (node (ref "SJ1") (pin "1") (pinfunction "1_1") (pintype "passive"))
      (node (ref "TP5") (pin "TP") (pinfunction "TP_TP") (pintype "input"))
      (node (ref "U1") (pin "4") (pinfunction "GND_4") (pintype "power_in"))
      (node (ref "U1") (pin "9") (pinfunction "EXP_9") (pintype "passive"))
      (node (ref "U2") (pin "1") (pinfunction "GND_1") (pintype "power_in"))
      (node (ref "U2") (pin "28") (pinfunction "GND_28") (pintype "power_in"))
      (node (ref "U2") (pin "29_1") (pinfunction "GND_29_1") (pintype "power_in"))
      (node (ref "U2") (pin "29_2") (pinfunction "GND_29_2") (pintype "power_in"))
      (node (ref "U2") (pin "29_3") (pinfunction "GND_29_3") (pintype "power_in"))
      (node (ref "U2") (pin "29_4") (pinfunction "GND_29_4") (pintype "power_in"))
      (node (ref "U2") (pin "29_5") (pinfunction "GND_29_5") (pintype "power_in"))
      (node (ref "U2") (pin "29_6") (pinfunction "GND_29_6") (pintype "power_in"))
      (node (ref "U2") (pin "29_7") (pinfunction "GND_29_7") (pintype "power_in"))
      (node (ref "U2") (pin "29_8") (pinfunction "GND_29_8") (pintype "power_in"))
      (node (ref "U2") (pin "29_9") (pinfunction "GND_29_9") (pintype "power_in"))
      (node (ref "U3") (pin "13") (pinfunction "GND_13") (pintype "power_in"))
      (node (ref "U4") (pin "1") (pinfunction "CTG_1") (pintype "power_in"))
      (node (ref "U4") (pin "4") (pinfunction "GND_4") (pintype "power_in"))
      (node (ref "U4") (pin "6") (pinfunction "QSTRT_6") (pintype "input"))
      (node (ref "U4") (pin "9") (pinfunction "EP_9") (pintype "power_in"))
    )
    (net (code "14") (name "GPIO8") (class "Default")
      (node (ref "R1") (pin "1") (pinfunction "1_1") (pintype "passive"))
      (node (ref "U2") (pin "10") (pinfunction "IO8_10") (pintype "bidirectional"))
    )
    (net (code "15") (name "I2C_PW") (class "Default")
      (node (ref "C1") (pin "1") (pinfunction "1_1") (pintype "passive"))
      (node (ref "C2") (pin "1") (pinfunction "1_1") (pintype "passive"))
      (node (ref "R1-PINH") (pin "2") (pinfunction "2_2") (pintype "passive"))
      (node (ref "R2-PINH") (pin "2") (pinfunction "2_2") (pintype "passive"))
      (node (ref "SENSOR2") (pin "2") (pinfunction "CSB_2") (pintype "input"))
      (node (ref "SENSOR2") (pin "6") (pinfunction "VDDIO_6") (pintype "power_in"))
      (node (ref "SENSOR2") (pin "8") (pinfunction "VDD_8") (pintype "power_in"))
      (node (ref "U2") (pin "17") (pinfunction "IO19_17") (pintype "bidirectional"))
    )
    (net (code "16") (name "INT_RTC") (class "Default")
      (node (ref "INT_RTC") (pin "TP") (pinfunction "TP_TP") (pintype "input"))
      (node (ref "R1-PINH1") (pin "1") (pinfunction "1_1") (pintype "passive"))
      (node (ref "U2") (pin "8") (pinfunction "IO0_8") (pintype "bidirectional"))
      (node (ref "U3") (pin "3") (pinfunction "SQW/~{INT}_3") (pintype "output"))
    )
    (net (code "17") (name "IO{slash}BOOT") (class "Default")
      (node (ref "BOOT_BUTTON") (pin "3") (pinfunction "3_3") (pintype "passive"))
      (node (ref "BOOT_BUTTON") (pin "4") (pinfunction "4_4") (pintype "passive"))
      (node (ref "C6") (pin "1") (pinfunction "1_1") (pintype "passive"))
      (node (ref "R_BOOT") (pin "1") (pinfunction "1_1") (pintype "passive"))
      (node (ref "U2") (pin "15") (pinfunction "IO9_15") (pintype "bidirectional"))
    )
    (net (code "18") (name "IO{slash}CHANGE") (class "Default")
      (node (ref "C10") (pin "1") (pinfunction "1_1") (pintype "passive"))
      (node (ref "CHANGE_BUTTON") (pin "3") (pinfunction "3_3") (pintype "passive"))
      (node (ref "CHANGE_BUTTON") (pin "4") (pinfunction "4_4") (pintype "passive"))
      (node (ref "R_CHANGE") (pin "1") (pinfunction "1_1") (pintype "passive"))
      (node (ref "U2") (pin "23") (pinfunction "IO15_23") (pintype "bidirectional"))
    )
    (net (code "19") (name "MISO") (class "Default")
      (node (ref "D12") (pin "2") (pinfunction "2_2") (pintype "passive"))
      (node (ref "J4") (pin "P7") (pinfunction "DAT0_P7") (pintype "bidirectional"))
      (node (ref "MISO") (pin "TP") (pinfunction "TP_TP") (pintype "input"))
      (node (ref "R8") (pin "1") (pinfunction "1_1") (pintype "passive"))
      (node (ref "U1") (pin "2") (pinfunction "DO(IO1)_2") (pintype "bidirectional"))
      (node (ref "U2") (pin "27") (pinfunction "IO2_27") (pintype "bidirectional"))
    )
    (net (code "20") (name "MOSI") (class "Default")
      (node (ref "D11") (pin "2") (pinfunction "2_2") (pintype "passive"))
      (node (ref "J1") (pin "14") (pinfunction "14_14") (pintype "bidirectional"))
      (node (ref "J4") (pin "P3") (pinfunction "CMD_P3") (pintype "bidirectional"))
      (node (ref "MOSI") (pin "TP") (pinfunction "TP_TP") (pintype "input"))
      (node (ref "R7") (pin "1") (pinfunction "1_1") (pintype "passive"))
      (node (ref "U1") (pin "5") (pinfunction "DI(IO0)_5") (pintype "bidirectional"))
      (node (ref "U2") (pin "7") (pinfunction "IO7_7") (pintype "bidirectional"))
    )
    (net (code "21") (name "Net-(CHG_LED-PadC)") (class "Default")
      (node (ref "CHG_LED") (pin "C") (pinfunction "C_C") (pintype "passive"))
      (node (ref "R1_BAT") (pin "1") (pinfunction "1_1") (pintype "passive"))
    )
    (net (code "22") (name "Net-(D2-CATHODE)") (class "Default")
      (node (ref "C1_BAT1") (pin "1") (pinfunction "1_1") (pintype "passive"))
      (node (ref "D2") (pin "1") (pinfunction "CATHODE_1") (pintype "bidirectional"))
      (node (ref "IC4") (pin "1") (pinfunction "VIN_1") (pintype "bidirectional"))
      (node (ref "IC4") (pin "3") (pinfunction "CE_3") (pintype "bidirectional"))
      (node (ref "Q1") (pin "2") (pinfunction "S_2") (pintype "bidirectional"))
    )
    (net (code "23") (name "Net-(D3-A)") (class "Default")
      (node (ref "C4") (pin "1") (pinfunction "1_1") (pintype "passive"))
      (node (ref "D3") (pin "2") (pinfunction "A_2") (pintype "bidirectional"))
      (node (ref "D4") (pin "1") (pinfunction "K_1") (pintype "bidirectional"))
    )
    (net (code "24") (name "Net-(D7-CATHODE)") (class "Default")
      (node (ref "D7") (pin "1") (pinfunction "CATHODE_1") (pintype "bidirectional"))
      (node (ref "R_CAPACITOR") (pin "1") (pinfunction "1_1") (pintype "passive"))
    )
    (net (code "25") (name "Net-(EPD_C1-Pad2)") (class "Default")
      (node (ref "EPD_C1") (pin "2") (pinfunction "2_2") (pintype "passive"))
      (node (ref "J1") (pin "4") (pinfunction "4_4") (pintype "bidirectional"))
    )
    (net (code "26") (name "Net-(EPD_C2-Pad2)") (class "Default")
      (node (ref "EPD_C2") (pin "2") (pinfunction "2_2") (pintype "passive"))
      (node (ref "J1") (pin "5") (pinfunction "5_5") (pintype "bidirectional"))
    )
    (net (code "27") (name "Net-(EPD_C6-Pad2)") (class "Default")
      (node (ref "EPD_C6") (pin "2") (pinfunction "2_2") (pintype "passive"))
      (node (ref "J1") (pin "18") (pinfunction "18_18") (pintype "bidirectional"))
    )
    (net (code "28") (name "Net-(EPD_C7-Pad2)") (class "Default")
      (node (ref "EPD_C7") (pin "2") (pinfunction "2_2") (pintype "passive"))
      (node (ref "J1") (pin "19") (pinfunction "19_19") (pintype "bidirectional"))
    )
    (net (code "29") (name "Net-(EPD_C8-Pad2)") (class "Default")
      (node (ref "EPD_C8") (pin "2") (pinfunction "2_2") (pintype "passive"))
      (node (ref "J1") (pin "20") (pinfunction "20_20") (pintype "bidirectional"))
    )
    (net (code "30") (name "Net-(EPD_C10-Pad2)") (class "Default")
      (node (ref "EPD_C10") (pin "2") (pinfunction "2_2") (pintype "passive"))
      (node (ref "J1") (pin "22") (pinfunction "22_22") (pintype "bidirectional"))
    )
    (net (code "31") (name "Net-(EPD_C12-Pad2)") (class "Default")
      (node (ref "EPD_C12") (pin "2") (pinfunction "2_2") (pintype "passive"))
      (node (ref "J1") (pin "24") (pinfunction "24_24") (pintype "bidirectional"))
    )
    (net (code "32") (name "Net-(IC1-CT)") (class "Default")
      (node (ref "C_DELAY") (pin "1") (pinfunction "1_1") (pintype "passive"))
      (node (ref "IC1") (pin "5") (pinfunction "CT_5") (pintype "bidirectional"))
    )
    (net (code "33") (name "Net-(J2-PadA5)") (class "Default")
      (node (ref "J2") (pin "A5") (pinfunction "A5_A5") (pintype "bidirectional"))
      (node (ref "R2-USB1") (pin "2") (pinfunction "2_2") (pintype "passive"))
    )
    (net (code "34") (name "Net-(J2-PadB5)") (class "Default")
      (node (ref "J2") (pin "B5") (pinfunction "B5_B5") (pintype "bidirectional"))
      (node (ref "R2-USB") (pin "1") (pinfunction "1_1") (pintype "passive"))
    )
    (net (code "35") (name "Net-(MCP73831-PROG)") (class "Default")
      (node (ref "MCP73831") (pin "5") (pinfunction "PROG_5") (pintype "input"))
      (node (ref "R2_BAT") (pin "2") (pinfunction "2_2") (pintype "passive"))
    )
    (net (code "36") (name "Net-(MCP73831-STAT)") (class "Default")
      (node (ref "MCP73831") (pin "1") (pinfunction "STAT_1") (pintype "output"))
      (node (ref "R1_BAT") (pin "2") (pinfunction "2_2") (pintype "passive"))
    )
    (net (code "37") (name "PREVGH") (class "Default")
      (node (ref "D5") (pin "1") (pinfunction "K_1") (pintype "bidirectional"))
      (node (ref "EPD_C9") (pin "2") (pinfunction "2_2") (pintype "passive"))
      (node (ref "J1") (pin "21") (pinfunction "21_21") (pintype "bidirectional"))
    )
    (net (code "38") (name "PREVGL") (class "Default")
      (node (ref "D4") (pin "2") (pinfunction "A_2") (pintype "bidirectional"))
      (node (ref "EPD_C11") (pin "2") (pinfunction "2_2") (pintype "passive"))
      (node (ref "J1") (pin "23") (pinfunction "23_23") (pintype "bidirectional"))
    )
    (net (code "39") (name "RESE") (class "Default")
      (node (ref "J1") (pin "3") (pinfunction "3_3") (pintype "bidirectional"))
      (node (ref "Q3") (pin "2") (pinfunction "S_2") (pintype "bidirectional"))
      (node (ref "R3") (pin "2") (pinfunction "2_2") (pintype "passive"))
    )
    (net (code "40") (name "RESE'") (class "Default")
      (node (ref "R2") (pin "2") (pinfunction "2_2") (pintype "passive"))
      (node (ref "R3") (pin "1") (pinfunction "1_1") (pintype "passive"))
      (node (ref "SJ1") (pin "2") (pinfunction "2_2") (pintype "passive"))
    )
    (net (code "41") (name "RESET") (class "Default")
      (node (ref "C5") (pin "1") (pinfunction "1_1") (pintype "passive"))
      (node (ref "IC1") (pin "1") (pinfunction "VOUT_1") (pintype "bidirectional"))
      (node (ref "RESET_BUTTON") (pin "3") (pinfunction "3_3") (pintype "passive"))
      (node (ref "RESET_BUTTON") (pin "4") (pinfunction "4_4") (pintype "passive"))
      (node (ref "R_RESET") (pin "1") (pinfunction "1_1") (pintype "passive"))
      (node (ref "U2") (pin "3") (pinfunction "EN_3") (pintype "input"))
    )
    (net (code "42") (name "RTC_RST") (class "Default")
      (node (ref "U2") (pin "16") (pinfunction "IO18_16") (pintype "bidirectional"))
      (node (ref "U3") (pin "4") (pinfunction "~{RST}_4") (pintype "input"))
    )
    (net (code "43") (name "RX") (class "Default")
      (node (ref "RX") (pin "TP") (pinfunction "TP_TP") (pintype "input"))
      (node (ref "U2") (pin "24") (pinfunction "RXD0/GPIO17_24") (pintype "bidirectional"))
    )
    (net (code "44") (name "SCK") (class "Default")
      (node (ref "D10") (pin "2") (pinfunction "2_2") (pintype "passive"))
      (node (ref "J1") (pin "13") (pinfunction "13_13") (pintype "bidirectional"))
      (node (ref "J4") (pin "P5") (pinfunction "CLK_P5") (pintype "bidirectional"))
      (node (ref "R6") (pin "1") (pinfunction "1_1") (pintype "passive"))
      (node (ref "SCK") (pin "TP") (pinfunction "TP_TP") (pintype "input"))
      (node (ref "U1") (pin "6") (pinfunction "CLK_6") (pintype "input"))
      (node (ref "U2") (pin "6") (pinfunction "IO6_6") (pintype "bidirectional"))
    )
    (net (code "45") (name "SCL") (class "Default")
      (node (ref "J3") (pin "4") (pinfunction "4_4") (pintype "passive"))
      (node (ref "R2-PINH") (pin "1") (pinfunction "1_1") (pintype "passive"))
      (node (ref "SENSOR2") (pin "4") (pinfunction "SCK_4") (pintype "input"))
      (node (ref "U2") (pin "20") (pinfunction "IO22_20") (pintype "bidirectional"))
      (node (ref "U3") (pin "16") (pinfunction "SCL_16") (pintype "input"))
      (node (ref "U4") (pin "7") (pinfunction "SCL_7") (pintype "input"))
    )
    (net (code "46") (name "SDA") (class "Default")
      (node (ref "J3") (pin "3") (pinfunction "3_3") (pintype "passive"))
      (node (ref "R1-PINH") (pin "1") (pinfunction "1_1") (pintype "passive"))
      (node (ref "SENSOR2") (pin "3") (pinfunction "SDI_3") (pintype "bidirectional"))
      (node (ref "U2") (pin "19") (pinfunction "IO21_19") (pintype "bidirectional"))
      (node (ref "U3") (pin "15") (pinfunction "SDA_15") (pintype "bidirectional"))
      (node (ref "U4") (pin "8") (pinfunction "SDA_8") (pintype "bidirectional"))
    )
    (net (code "47") (name "SRC") (class "Default")
      (node (ref "C4") (pin "2") (pinfunction "2_2") (pintype "passive"))
      (node (ref "D5") (pin "2") (pinfunction "A_2") (pintype "bidirectional"))
      (node (ref "L1") (pin "1") (pinfunction "1_1") (pintype "passive"))
      (node (ref "Q3") (pin "3") (pinfunction "D_3") (pintype "bidirectional"))
    )
    (net (code "48") (name "SS_SD") (class "Default")
      (node (ref "D8") (pin "2") (pinfunction "2_2") (pintype "passive"))
      (node (ref "J4") (pin "P2") (pinfunction "CD/DAT3_P2") (pintype "bidirectional"))
      (node (ref "R10") (pin "1") (pinfunction "1_1") (pintype "passive"))
      (node (ref "U2") (pin "4") (pinfunction "IO4_4") (pintype "bidirectional"))
    )
    (net (code "49") (name "TX") (class "Default")
      (node (ref "TX") (pin "TP") (pinfunction "TP_TP") (pintype "input"))
      (node (ref "U2") (pin "25") (pinfunction "TXD0/GPIO16_25") (pintype "bidirectional"))
    )
    (net (code "50") (name "USB_D+") (class "Default")
      (node (ref "D1") (pin "4") (pinfunction "I/O2_2_4") (pintype "bidirectional"))
      (node (ref "U2") (pin "14") (pinfunction "IO13_14") (pintype "bidirectional"))
    )
    (net (code "51") (name "USB_D-") (class "Default")
      (node (ref "D1") (pin "6") (pinfunction "I/O1_2_6") (pintype "bidirectional"))
      (node (ref "U2") (pin "13") (pinfunction "IO12_13") (pintype "bidirectional"))
    )
    (net (code "52") (name "VBAT") (class "Default")
      (node (ref "C2_BAT") (pin "1") (pinfunction "1_1") (pintype "passive"))
      (node (ref "MCP73831") (pin "3") (pinfunction "VBAT_3") (pintype "power_in"))
      (node (ref "Q1") (pin "3") (pinfunction "D_3") (pintype "bidirectional"))
      (node (ref "U4") (pin "2") (pinfunction "CELL_2") (pintype "power_in"))
      (node (ref "U4") (pin "3") (pinfunction "VDD_3") (pintype "power_in"))
      (node (ref "VBAT") (pin "TP") (pinfunction "TP_TP") (pintype "input"))
    )
    (net (code "53") (name "VBUS") (class "Default")
      (node (ref "C1_BAT") (pin "1") (pinfunction "1_1") (pintype "passive"))
      (node (ref "C4_USB") (pin "1") (pinfunction "1_1") (pintype "passive"))
      (node (ref "C5_USB") (pin "1") (pinfunction "1_1") (pintype "passive"))
      (node (ref "CHG_LED") (pin "A") (pinfunction "A_A") (pintype "passive"))
      (node (ref "D1") (pin "2") (pinfunction "GND_2") (pintype "bidirectional"))
      (node (ref "D2") (pin "2") (pinfunction "ANODE_2") (pintype "bidirectional"))
      (node (ref "MCP73831") (pin "4") (pinfunction "VIN_4") (pintype "power_in"))
      (node (ref "PFMF.050.1") (pin "2") (pinfunction "2_2") (pintype "passive"))
      (node (ref "Q1") (pin "1") (pinfunction "G_1") (pintype "bidirectional"))
      (node (ref "R1_PWRUSB") (pin "2") (pinfunction "2_2") (pintype "passive"))
      (node (ref "VBUS") (pin "TP") (pinfunction "TP_TP") (pintype "input"))
    )
    (net (code "54") (name "VRTC") (class "Default")
      (node (ref "C10_SUPERCAP") (pin "2") (pinfunction "2_2") (pintype "passive"))
      (node (ref "C8") (pin "1") (pinfunction "1_1") (pintype "passive"))
      (node (ref "R_CAPACITOR") (pin "2") (pinfunction "2_2") (pintype "passive"))
      (node (ref "U3") (pin "14") (pinfunction "VBAT_14") (pintype "power_in"))
    )
    (net (code "55") (name "VUSB") (class "Default")
      (node (ref "J2") (pin "A4") (pinfunction "A4_A4") (pintype "bidirectional"))
      (node (ref "J2") (pin "A9") (pinfunction "A9_A9") (pintype "bidirectional"))
      (node (ref "J2") (pin "B4") (pinfunction "B4_B4") (pintype "bidirectional"))
      (node (ref "J2") (pin "B9") (pinfunction "B9_B9") (pintype "bidirectional"))
      (node (ref "PFMF.050.1") (pin "1") (pinfunction "1_1") (pintype "passive"))
    )
    (net (code "56") (name "unconnected-(IC1-NC-Pad4)") (class "Default")
      (node (ref "IC1") (pin "4") (pinfunction "NC_4") (pintype "no_connect"))
    )
    (net (code "57") (name "unconnected-(IC4-NC-Pad4)") (class "Default")
      (node (ref "IC4") (pin "4") (pinfunction "NC_4") (pintype "no_connect"))
    )
    (net (code "58") (name "unconnected-(J1-Pad1)") (class "Default")
      (node (ref "J1") (pin "1") (pinfunction "1_1") (pintype "bidirectional"))
    )
    (net (code "59") (name "unconnected-(J1-Pad6)") (class "Default")
      (node (ref "J1") (pin "6") (pinfunction "6_6") (pintype "bidirectional"))
    )
    (net (code "60") (name "unconnected-(J1-Pad7)") (class "Default")
      (node (ref "J1") (pin "7") (pinfunction "7_7") (pintype "bidirectional"))
    )
    (net (code "61") (name "unconnected-(J2-PadA8)") (class "Default")
      (node (ref "J2") (pin "A8") (pinfunction "A8_A8") (pintype "bidirectional"))
    )
    (net (code "62") (name "unconnected-(J2-PadB8)") (class "Default")
      (node (ref "J2") (pin "B8") (pinfunction "B8_B8") (pintype "bidirectional"))
    )
    (net (code "63") (name "unconnected-(J4-DAT1-PadP8)") (class "Default")
      (node (ref "J4") (pin "P8") (pinfunction "DAT1_P8") (pintype "bidirectional"))
    )
    (net (code "64") (name "unconnected-(J4-DAT2-PadP1)") (class "Default")
      (node (ref "J4") (pin "P1") (pinfunction "DAT2_P1") (pintype "bidirectional"))
    )
    (net (code "65") (name "unconnected-(J4-DETECTION_1-PadS1)") (class "Default")
      (node (ref "J4") (pin "S1") (pinfunction "DETECTION_1_S1") (pintype "bidirectional"))
    )
    (net (code "66") (name "unconnected-(J4-DETECTION_2-PadS2)") (class "Default")
      (node (ref "J4") (pin "S2") (pinfunction "DETECTION_2_S2") (pintype "bidirectional"))
    )
    (net (code "67") (name "unconnected-(U2-NC-Pad22)") (class "Default")
      (node (ref "U2") (pin "22") (pinfunction "NC_22") (pintype "no_connect"))
    )
    (net (code "68") (name "unconnected-(U4-~{ALERT}-Pad5)") (class "Default")
      (node (ref "U4") (pin "5") (pinfunction "~{ALERT}_5") (pintype "output"))
    )
  )
)
